# Main_Core.net
KiCad netlist of a schematic drawn in Altium Designer
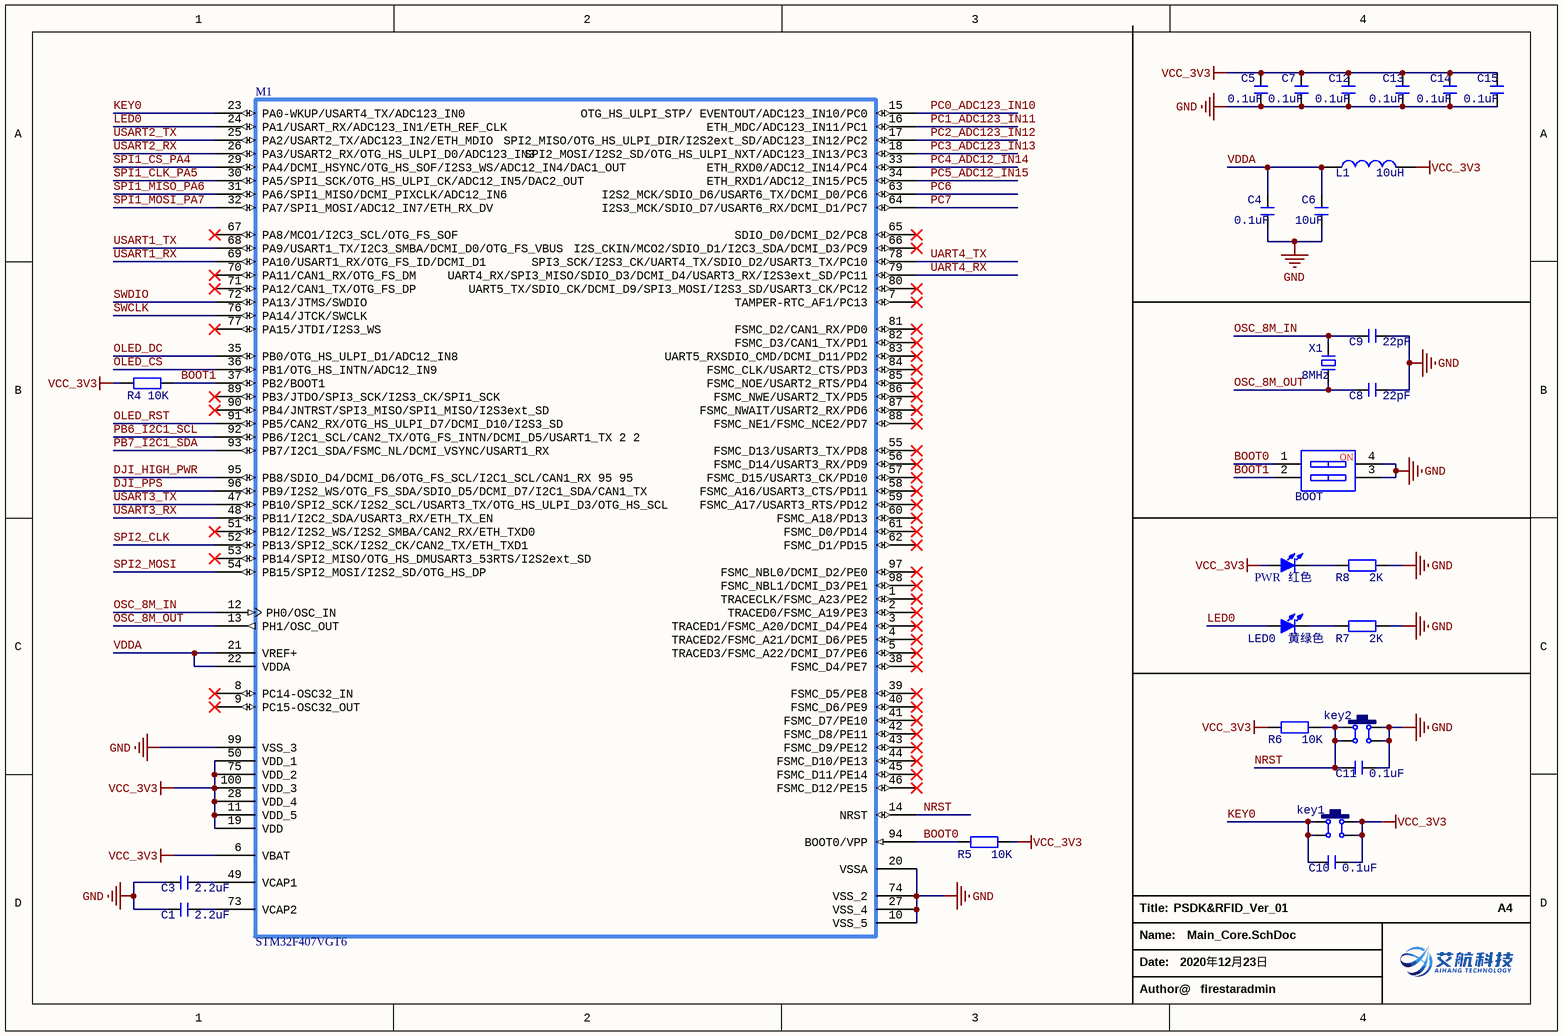
[diagram p0: Main_Core.SchDoc]

(export (version "E")
  (design (tool "Eeschema 10.0.6"))
  (components
    (comp (ref "BOOT")
      (value "CSW-2P")
      (footprint "CSW1.27 SMD-2P")
      (description "2路编码开关")
      (fields (field (name "版权归属") "源创客"))
      (libsource (lib "SCH-按键-开关") (part "CSW-2P"))
    )
    (comp (ref "C1")
      (value "2.2uF")
      (footprint "C 0603_L")
      (description "无极性贴片电容")
      (fields (field (name "版权归属") "源创客"))
      (libsource (lib "SCH-电阻-电容-电感") (part "C"))
    )
    (comp (ref "C3")
      (value "2.2uF")
      (footprint "C 0603_L")
      (description "无极性贴片电容")
      (fields (field (name "版权归属") "源创客"))
      (libsource (lib "SCH-电阻-电容-电感") (part "C"))
    )
    (comp (ref "C4")
      (value "0.1uF")
      (footprint "C 0603_L")
      (description "无极性贴片电容")
      (fields (field (name "版权归属") "源创客"))
      (libsource (lib "SCH-电阻-电容-电感") (part "C"))
    )
    (comp (ref "C5")
      (value "0.1uF")
      (footprint "C 0603_L")
      (description "无极性贴片电容")
      (fields (field (name "版权归属") "源创客"))
      (libsource (lib "SCH-电阻-电容-电感") (part "C"))
    )
    (comp (ref "C6")
      (value "10uF")
      (footprint "C 0603_L")
      (description "无极性贴片电容")
      (fields (field (name "版权归属") "源创客"))
      (libsource (lib "SCH-电阻-电容-电感") (part "C"))
    )
    (comp (ref "C7")
      (value "0.1uF")
      (footprint "C 0603_L")
      (description "无极性贴片电容")
      (fields (field (name "版权归属") "源创客"))
      (libsource (lib "SCH-电阻-电容-电感") (part "C"))
    )
    (comp (ref "C8")
      (value "22pF")
      (footprint "C 0603_L")
      (description "无极性贴片电容")
      (fields (field (name "版权归属") "源创客"))
      (libsource (lib "SCH-电阻-电容-电感") (part "C"))
    )
    (comp (ref "C9")
      (value "22pF")
      (footprint "C 0603_L")
      (description "无极性贴片电容")
      (fields (field (name "版权归属") "源创客"))
      (libsource (lib "SCH-电阻-电容-电感") (part "C"))
    )
    (comp (ref "C10")
      (value "0.1uF")
      (footprint "C 0603_L")
      (description "无极性贴片电容")
      (fields (field (name "版权归属") "源创客"))
      (libsource (lib "SCH-电阻-电容-电感") (part "C"))
    )
    (comp (ref "C11")
      (value "0.1uF")
      (footprint "C 0603_L")
      (description "无极性贴片电容")
      (fields (field (name "版权归属") "源创客"))
      (libsource (lib "SCH-电阻-电容-电感") (part "C"))
    )
    (comp (ref "C12")
      (value "0.1uF")
      (footprint "C 0603_L")
      (description "无极性贴片电容")
      (fields (field (name "版权归属") "源创客"))
      (libsource (lib "SCH-电阻-电容-电感") (part "C"))
    )
    (comp (ref "C13")
      (value "0.1uF")
      (footprint "C 0603_L")
      (description "无极性贴片电容")
      (fields (field (name "版权归属") "源创客"))
      (libsource (lib "SCH-电阻-电容-电感") (part "C"))
    )
    (comp (ref "C14")
      (value "0.1uF")
      (footprint "C 0603_L")
      (description "无极性贴片电容")
      (fields (field (name "版权归属") "源创客"))
      (libsource (lib "SCH-电阻-电容-电感") (part "C"))
    )
    (comp (ref "C15")
      (value "0.1uF")
      (footprint "C 0603_L")
      (description "无极性贴片电容")
      (fields (field (name "版权归属") "源创客"))
      (libsource (lib "SCH-电阻-电容-电感") (part "C"))
    )
    (comp (ref "key1")
      (value "key")
      (footprint "TSMD-3*4*2.5")
      (description "TS-3x4x2.5mm-4pin 轻触按键")
      (libsource (lib "SCH-按键-开关") (part "TS-3x4x2.5mm-4pin"))
    )
    (comp (ref "key2")
      (value "key")
      (footprint "TSMD-3*4*2.5")
      (description "TS-3x4x2.5mm-4pin 轻触按键")
      (libsource (lib "SCH-按键-开关") (part "TS-3x4x2.5mm-4pin"))
    )
    (comp (ref "L1")
      (value "10uH")
      (footprint "L 0603")
      (description "小功率贴片电感")
      (fields (field (name "版权归属") "源创客"))
      (libsource (lib "SCH-电阻-电容-电感") (part "L"))
    )
    (comp (ref "LED0")
      (value "黄绿色")
      (footprint "LED 0603G")
      (description "贴片LED")
      (fields (field (name "版权归属") "源创客"))
      (libsource (lib "SCH-LED") (part "LED-SMD"))
    )
    (comp (ref "M1")
      (value "STM32F407VGT6")
      (footprint "LQFP100 14x14_M")
      (description "LQFP100，ARM®-Cortex®-M4-series-微控制器-IC-32-位-168MHz-1MB Flash，192KB SRAM.  IO:82")
      (libsource (lib "SCH-STM32系列单片机") (part "STM32F407VGT6"))
    )
    (comp (ref "PWR")
      (value "红色")
      (footprint "LED 0603R")
      (description "贴片LED")
      (fields (field (name "版权归属") "源创客"))
      (libsource (lib "SCH-LED") (part "LED-SMD"))
    )
    (comp (ref "R4")
      (value "10K")
      (footprint "R 0603_L")
      (description "贴片电阻")
      (fields (field (name "版权归属") "源创客"))
      (libsource (lib "SCH-电阻-电容-电感") (part "R"))
    )
    (comp (ref "R5")
      (value "10K")
      (footprint "R 0603_L")
      (description "贴片电阻")
      (fields (field (name "版权归属") "源创客"))
      (libsource (lib "SCH-电阻-电容-电感") (part "R"))
    )
    (comp (ref "R6")
      (value "10K")
      (footprint "R 0603_L")
      (description "贴片电阻")
      (fields (field (name "版权归属") "源创客"))
      (libsource (lib "SCH-电阻-电容-电感") (part "R"))
    )
    (comp (ref "R7")
      (value "2K")
      (footprint "R 0603_L")
      (description "贴片电阻")
      (fields (field (name "版权归属") "源创客"))
      (libsource (lib "SCH-电阻-电容-电感") (part "R"))
    )
    (comp (ref "R8")
      (value "2K")
      (footprint "R 0603_L")
      (description "贴片电阻")
      (fields (field (name "版权归属") "源创客"))
      (libsource (lib "SCH-电阻-电容-电感") (part "R"))
    )
    (comp (ref "X1")
      (value "8MHz")
      (footprint "OSC 5032-2P")
      (description "2脚无源脚晶振")
      (fields (field (name "版权归属") "源创客"))
      (libsource (lib "SCH- 保险丝-晶振") (part "XTAL-2P"))
    )
  )
  (nets
    (net (code "1") (name "/BOOT0") (class "Default")
      (node (ref "BOOT") (pin "1") (pinfunction "1_1") (pintype "passive"))
      (node (ref "M1") (pin "94") (pinfunction "BOOT0/VPP_94") (pintype "input"))
      (node (ref "R5") (pin "1") (pinfunction "1_1") (pintype "passive"))
    )
    (net (code "2") (name "/BOOT1") (class "Default")
      (node (ref "BOOT") (pin "2") (pinfunction "2_2") (pintype "passive"))
      (node (ref "M1") (pin "37") (pinfunction "PB2/BOOT1_37") (pintype "bidirectional"))
      (node (ref "R4") (pin "1") (pinfunction "1_1") (pintype "passive"))
    )
    (net (code "3") (name "/DJI_HIGH_PWR") (class "Default")
      (node (ref "M1") (pin "95") (pinfunction "PB8/SDIO_D4/DCMI_D6/OTG_FS_SCL/I2C1_SCL/CAN1_RX_95_95_95") (pintype "bidirectional"))
    )
    (net (code "4") (name "/DJI_PPS") (class "Default")
      (node (ref "M1") (pin "96") (pinfunction "PB9/I2S2_WS/OTG_FS_SDA/SDIO_D5/DCMI_D7/I2C1_SDA/CAN1_TX_96") (pintype "bidirectional"))
    )
    (net (code "5") (name "/KEY0") (class "Default")
      (node (ref "C10") (pin "2") (pinfunction "2_2") (pintype "passive"))
      (node (ref "M1") (pin "23") (pinfunction "PA0-WKUP/USART4_TX/ADC123_IN0_23") (pintype "bidirectional"))
      (node (ref "key1") (pin "1") (pinfunction "1_1") (pintype "passive"))
      (node (ref "key1") (pin "2") (pinfunction "2_2") (pintype "passive"))
    )
    (net (code "6") (name "/LED0") (class "Default")
      (node (ref "LED0") (pin "1") (pinfunction "A_1") (pintype "passive"))
      (node (ref "M1") (pin "24") (pinfunction "PA1/USART_RX/ADC123_IN1/ETH_REF_CLK_24") (pintype "bidirectional"))
    )
    (net (code "7") (name "/NRST") (class "Default")
      (node (ref "C11") (pin "2") (pinfunction "2_2") (pintype "passive"))
      (node (ref "M1") (pin "14") (pinfunction "NRST_14") (pintype "bidirectional"))
      (node (ref "R6") (pin "2") (pinfunction "2_2") (pintype "passive"))
      (node (ref "key2") (pin "1") (pinfunction "1_1") (pintype "passive"))
      (node (ref "key2") (pin "2") (pinfunction "2_2") (pintype "passive"))
    )
    (net (code "8") (name "/OLED_CS") (class "Default")
      (node (ref "M1") (pin "36") (pinfunction "PB1/OTG_HS_INTN/ADC12_IN9_36") (pintype "bidirectional"))
    )
    (net (code "9") (name "/OLED_DC") (class "Default")
      (node (ref "M1") (pin "35") (pinfunction "PB0/OTG_HS_ULPI_D1/ADC12_IN8_35") (pintype "bidirectional"))
    )
    (net (code "10") (name "/OLED_RST") (class "Default")
      (node (ref "M1") (pin "91") (pinfunction "PB5/CAN2_RX/OTG_HS_ULPI_D7/DCMI_D10/I2S3_SD_91") (pintype "bidirectional"))
    )
    (net (code "11") (name "/OSC_8M_IN") (class "Default")
      (node (ref "C9") (pin "2") (pinfunction "2_2") (pintype "passive"))
      (node (ref "M1") (pin "12") (pinfunction "PH0/OSC_IN_12") (pintype "input"))
      (node (ref "X1") (pin "2") (pinfunction "2_2") (pintype "passive"))
    )
    (net (code "12") (name "/OSC_8M_OUT") (class "Default")
      (node (ref "C8") (pin "2") (pinfunction "2_2") (pintype "passive"))
      (node (ref "M1") (pin "13") (pinfunction "PH1/OSC_OUT_13") (pintype "output"))
      (node (ref "X1") (pin "1") (pinfunction "1_1") (pintype "passive"))
    )
    (net (code "13") (name "/PB6_I2C1_SCL") (class "Default")
      (node (ref "M1") (pin "92") (pinfunction "PB6/I2C1_SCL/CAN2_TX/OTG_FS_INTN/DCMI_D5/USART1_TX_2_2_92") (pintype "bidirectional"))
    )
    (net (code "14") (name "/PB7_I2C1_SDA") (class "Default")
      (node (ref "M1") (pin "93") (pinfunction "PB7/I2C1_SDA/FSMC_NL/DCMI_VSYNC/USART1_RX_93") (pintype "bidirectional"))
    )
    (net (code "15") (name "/PC0_ADC123_IN10") (class "Default")
      (node (ref "M1") (pin "15") (pinfunction "OTG_HS_ULPI_STP/_EVENTOUT/ADC123_IN10/PC0_15") (pintype "bidirectional"))
    )
    (net (code "16") (name "/PC1_ADC123_IN11") (class "Default")
      (node (ref "M1") (pin "16") (pinfunction "ETH_MDC/ADC123_IN11/PC1_16") (pintype "bidirectional"))
    )
    (net (code "17") (name "/PC2_ADC123_IN12") (class "Default")
      (node (ref "M1") (pin "17") (pinfunction "SPI2_MISO/OTG_HS_ULPI_DIR/I2S2ext_SD/ADC123_IN12/PC2_17") (pintype "bidirectional"))
    )
    (net (code "18") (name "/PC3_ADC123_IN13") (class "Default")
      (node (ref "M1") (pin "18") (pinfunction "SPI2_MOSI/I2S2_SD/OTG_HS_ULPI_NXT/ADC123_IN13/PC3_18") (pintype "bidirectional"))
    )
    (net (code "19") (name "/PC4_ADC12_IN14") (class "Default")
      (node (ref "M1") (pin "33") (pinfunction "ETH_RXD0/ADC12_IN14/PC4_33") (pintype "bidirectional"))
    )
    (net (code "20") (name "/PC5_ADC12_IN15") (class "Default")
      (node (ref "M1") (pin "34") (pinfunction "ETH_RXD1/ADC12_IN15/PC5_34") (pintype "bidirectional"))
    )
    (net (code "21") (name "/PC6") (class "Default")
      (node (ref "M1") (pin "63") (pinfunction "I2S2_MCK/SDIO_D6/USART6_TX/DCMI_D0/PC6_63") (pintype "bidirectional"))
    )
    (net (code "22") (name "/PC7") (class "Default")
      (node (ref "M1") (pin "64") (pinfunction "I2S3_MCK/SDIO_D7/USART6_RX/DCMI_D1/PC7_64") (pintype "bidirectional"))
    )
    (net (code "23") (name "/SPI1_CLK_PA5") (class "Default")
      (node (ref "M1") (pin "30") (pinfunction "PA5/SPI1_SCK/OTG_HS_ULPI_CK/ADC12_IN5/DAC2_OUT_30") (pintype "bidirectional"))
    )
    (net (code "24") (name "/SPI1_CS_PA4") (class "Default")
      (node (ref "M1") (pin "29") (pinfunction "PA4/DCMI_HSYNC/OTG_HS_SOF/I2S3_WS/ADC12_IN4/DAC1_OUT_29") (pintype "bidirectional"))
    )
    (net (code "25") (name "/SPI1_MISO_PA6") (class "Default")
      (node (ref "M1") (pin "31") (pinfunction "PA6/SPI1_MISO/DCMI_PIXCLK/ADC12_IN6_31") (pintype "bidirectional"))
    )
    (net (code "26") (name "/SPI1_MOSI_PA7") (class "Default")
      (node (ref "M1") (pin "32") (pinfunction "PA7/SPI1_MOSI/ADC12_IN7/ETH_RX_DV_32") (pintype "bidirectional"))
    )
    (net (code "27") (name "/SPI2_CLK") (class "Default")
      (node (ref "M1") (pin "52") (pinfunction "PB13/SPI2_SCK/I2S2_CK/CAN2_TX/ETH_TXD1_52") (pintype "bidirectional"))
    )
    (net (code "28") (name "/SPI2_MOSI") (class "Default")
      (node (ref "M1") (pin "54") (pinfunction "PB15/SPI2_MOSI/I2S2_SD/OTG_HS_DP_54") (pintype "bidirectional"))
    )
    (net (code "29") (name "/SWCLK") (class "Default")
      (node (ref "M1") (pin "76") (pinfunction "PA14/JTCK/SWCLK_76") (pintype "bidirectional"))
    )
    (net (code "30") (name "/SWDIO") (class "Default")
      (node (ref "M1") (pin "72") (pinfunction "PA13/JTMS/SWDIO_72") (pintype "bidirectional"))
    )
    (net (code "31") (name "/UART4_RX") (class "Default")
      (node (ref "M1") (pin "79") (pinfunction "UART4_RX/SPI3_MISO/SDIO_D3/DCMI_D4/USART3_RX/I2S3ext_SD/PC11_79") (pintype "bidirectional"))
    )
    (net (code "32") (name "/UART4_TX") (class "Default")
      (node (ref "M1") (pin "78") (pinfunction "SPI3_SCK/I2S3_CK/UART4_TX/SDIO_D2/USART3_TX/PC10_78") (pintype "bidirectional"))
    )
    (net (code "33") (name "/USART1_RX") (class "Default")
      (node (ref "M1") (pin "69") (pinfunction "PA10/USART1_RX/OTG_FS_ID/DCMI_D1_69") (pintype "bidirectional"))
    )
    (net (code "34") (name "/USART1_TX") (class "Default")
      (node (ref "M1") (pin "68") (pinfunction "PA9/USART1_TX/I2C3_SMBA/DCMI_D0/OTG_FS_VBUS_68") (pintype "bidirectional"))
    )
    (net (code "35") (name "/USART2_RX") (class "Default")
      (node (ref "M1") (pin "26") (pinfunction "PA3/USART2_RX/OTG_HS_ULPI_D0/ADC123_IN3_26") (pintype "bidirectional"))
    )
    (net (code "36") (name "/USART2_TX") (class "Default")
      (node (ref "M1") (pin "25") (pinfunction "PA2/USART2_TX/ADC123_IN2/ETH_MDIO_25") (pintype "bidirectional"))
    )
    (net (code "37") (name "/USART3_RX") (class "Default")
      (node (ref "M1") (pin "48") (pinfunction "PB11/I2C2_SDA/USART3_RX/ETH_TX_EN_48") (pintype "bidirectional"))
    )
    (net (code "38") (name "/USART3_TX") (class "Default")
      (node (ref "M1") (pin "47") (pinfunction "PB10/SPI2_SCK/I2S2_SCL/USART3_TX/OTG_HS_ULPI_D3/OTG_HS_SCL_47") (pintype "bidirectional"))
    )
    (net (code "39") (name "/VDDA") (class "Default")
      (node (ref "C4") (pin "2") (pinfunction "2_2") (pintype "passive"))
      (node (ref "C6") (pin "2") (pinfunction "2_2") (pintype "passive"))
      (node (ref "L1") (pin "1") (pinfunction "1_1") (pintype "passive"))
      (node (ref "M1") (pin "21") (pinfunction "VREF+_21") (pintype "power_in"))
      (node (ref "M1") (pin "22") (pinfunction "VDDA_22") (pintype "power_in"))
    )
    (net (code "40") (name "GND") (class "Default")
      (node (ref "BOOT") (pin "3") (pinfunction "3_3") (pintype "passive"))
      (node (ref "BOOT") (pin "4") (pinfunction "4_4") (pintype "passive"))
      (node (ref "C1") (pin "2") (pinfunction "2_2") (pintype "passive"))
      (node (ref "C11") (pin "1") (pinfunction "1_1") (pintype "passive"))
      (node (ref "C12") (pin "1") (pinfunction "1_1") (pintype "passive"))
      (node (ref "C13") (pin "1") (pinfunction "1_1") (pintype "passive"))
      (node (ref "C14") (pin "1") (pinfunction "1_1") (pintype "passive"))
      (node (ref "C15") (pin "1") (pinfunction "1_1") (pintype "passive"))
      (node (ref "C3") (pin "2") (pinfunction "2_2") (pintype "passive"))
      (node (ref "C4") (pin "1") (pinfunction "1_1") (pintype "passive"))
      (node (ref "C5") (pin "1") (pinfunction "1_1") (pintype "passive"))
      (node (ref "C6") (pin "1") (pinfunction "1_1") (pintype "passive"))
      (node (ref "C7") (pin "1") (pinfunction "1_1") (pintype "passive"))
      (node (ref "C8") (pin "1") (pinfunction "1_1") (pintype "passive"))
      (node (ref "C9") (pin "1") (pinfunction "1_1") (pintype "passive"))
      (node (ref "M1") (pin "10") (pinfunction "VSS_5_10") (pintype "power_in"))
      (node (ref "M1") (pin "20") (pinfunction "VSSA_20") (pintype "power_in"))
      (node (ref "M1") (pin "27") (pinfunction "VSS_4_27") (pintype "power_in"))
      (node (ref "M1") (pin "74") (pinfunction "VSS_2_74") (pintype "power_in"))
      (node (ref "M1") (pin "99") (pinfunction "VSS_3_99") (pintype "power_in"))
      (node (ref "R7") (pin "2") (pinfunction "2_2") (pintype "passive"))
      (node (ref "R8") (pin "2") (pinfunction "2_2") (pintype "passive"))
      (node (ref "key2") (pin "3") (pinfunction "3_3") (pintype "passive"))
      (node (ref "key2") (pin "4") (pinfunction "4_4") (pintype "passive"))
    )
    (net (code "41") (name "Net-(LED0-K)") (class "Default")
      (node (ref "LED0") (pin "2") (pinfunction "K_2") (pintype "passive"))
      (node (ref "R7") (pin "1") (pinfunction "1_1") (pintype "passive"))
    )
    (net (code "42") (name "Net-(M1-VCAP1)") (class "Default")
      (node (ref "C3") (pin "1") (pinfunction "1_1") (pintype "passive"))
      (node (ref "M1") (pin "49") (pinfunction "VCAP1_49") (pintype "power_in"))
    )
    (net (code "43") (name "Net-(M1-VCAP2)") (class "Default")
      (node (ref "C1") (pin "1") (pinfunction "1_1") (pintype "passive"))
      (node (ref "M1") (pin "73") (pinfunction "VCAP2_73") (pintype "passive"))
    )
    (net (code "44") (name "Net-(PWR-K)") (class "Default")
      (node (ref "PWR") (pin "2") (pinfunction "K_2") (pintype "passive"))
      (node (ref "R8") (pin "1") (pinfunction "1_1") (pintype "passive"))
    )
    (net (code "45") (name "VCC_3V3") (class "Default")
      (node (ref "C10") (pin "1") (pinfunction "1_1") (pintype "passive"))
      (node (ref "C12") (pin "2") (pinfunction "2_2") (pintype "passive"))
      (node (ref "C13") (pin "2") (pinfunction "2_2") (pintype "passive"))
      (node (ref "C14") (pin "2") (pinfunction "2_2") (pintype "passive"))
      (node (ref "C15") (pin "2") (pinfunction "2_2") (pintype "passive"))
      (node (ref "C5") (pin "2") (pinfunction "2_2") (pintype "passive"))
      (node (ref "C7") (pin "2") (pinfunction "2_2") (pintype "passive"))
      (node (ref "L1") (pin "2") (pinfunction "2_2") (pintype "passive"))
      (node (ref "M1") (pin "100") (pinfunction "VDD_3_100") (pintype "power_in"))
      (node (ref "M1") (pin "11") (pinfunction "VDD_5_11") (pintype "power_in"))
      (node (ref "M1") (pin "19") (pinfunction "VDD_19") (pintype "power_in"))
      (node (ref "M1") (pin "28") (pinfunction "VDD_4_28") (pintype "power_in"))
      (node (ref "M1") (pin "50") (pinfunction "VDD_1_50") (pintype "power_in"))
      (node (ref "M1") (pin "6") (pinfunction "VBAT_6") (pintype "power_in"))
      (node (ref "M1") (pin "75") (pinfunction "VDD_2_75") (pintype "power_in"))
      (node (ref "PWR") (pin "1") (pinfunction "A_1") (pintype "passive"))
      (node (ref "R4") (pin "2") (pinfunction "2_2") (pintype "passive"))
      (node (ref "R5") (pin "2") (pinfunction "2_2") (pintype "passive"))
      (node (ref "R6") (pin "1") (pinfunction "1_1") (pintype "passive"))
      (node (ref "key1") (pin "3") (pinfunction "3_3") (pintype "passive"))
      (node (ref "key1") (pin "4") (pinfunction "4_4") (pintype "passive"))
    )
    (net (code "46") (name "unconnected-(M1-FSMC_A16{slash}USART3_CTS{slash}PD11-Pad58)") (class "Default")
      (node (ref "M1") (pin "58") (pinfunction "FSMC_A16/USART3_CTS/PD11_58") (pintype "bidirectional+no_connect"))
    )
    (net (code "47") (name "unconnected-(M1-FSMC_A17{slash}USART3_RTS{slash}PD12-Pad59)") (class "Default")
      (node (ref "M1") (pin "59") (pinfunction "FSMC_A17/USART3_RTS/PD12_59") (pintype "bidirectional+no_connect"))
    )
    (net (code "48") (name "unconnected-(M1-FSMC_A18{slash}PD13-Pad60)") (class "Default")
      (node (ref "M1") (pin "60") (pinfunction "FSMC_A18/PD13_60") (pintype "bidirectional+no_connect"))
    )
    (net (code "49") (name "unconnected-(M1-FSMC_CLK{slash}USART2_CTS{slash}PD3-Pad84)") (class "Default")
      (node (ref "M1") (pin "84") (pinfunction "FSMC_CLK/USART2_CTS/PD3_84") (pintype "bidirectional+no_connect"))
    )
    (net (code "50") (name "unconnected-(M1-FSMC_D0{slash}PD14-Pad61)") (class "Default")
      (node (ref "M1") (pin "61") (pinfunction "FSMC_D0/PD14_61") (pintype "bidirectional+no_connect"))
    )
    (net (code "51") (name "unconnected-(M1-FSMC_D1{slash}PD15-Pad62)") (class "Default")
      (node (ref "M1") (pin "62") (pinfunction "FSMC_D1/PD15_62") (pintype "bidirectional+no_connect"))
    )
    (net (code "52") (name "unconnected-(M1-FSMC_D2{slash}CAN1_RX{slash}PD0-Pad81)") (class "Default")
      (node (ref "M1") (pin "81") (pinfunction "FSMC_D2/CAN1_RX/PD0_81") (pintype "bidirectional+no_connect"))
    )
    (net (code "53") (name "unconnected-(M1-FSMC_D3{slash}CAN1_TX{slash}PD1-Pad82)") (class "Default")
      (node (ref "M1") (pin "82") (pinfunction "FSMC_D3/CAN1_TX/PD1_82") (pintype "bidirectional+no_connect"))
    )
    (net (code "54") (name "unconnected-(M1-FSMC_D4{slash}PE7-Pad38)") (class "Default")
      (node (ref "M1") (pin "38") (pinfunction "FSMC_D4/PE7_38") (pintype "bidirectional+no_connect"))
    )
    (net (code "55") (name "unconnected-(M1-FSMC_D5{slash}PE8-Pad39)") (class "Default")
      (node (ref "M1") (pin "39") (pinfunction "FSMC_D5/PE8_39") (pintype "bidirectional+no_connect"))
    )
    (net (code "56") (name "unconnected-(M1-FSMC_D6{slash}PE9-Pad40)") (class "Default")
      (node (ref "M1") (pin "40") (pinfunction "FSMC_D6/PE9_40") (pintype "bidirectional+no_connect"))
    )
    (net (code "57") (name "unconnected-(M1-FSMC_D7{slash}PE10-Pad41)") (class "Default")
      (node (ref "M1") (pin "41") (pinfunction "FSMC_D7/PE10_41") (pintype "bidirectional+no_connect"))
    )
    (net (code "58") (name "unconnected-(M1-FSMC_D8{slash}PE11-Pad42)") (class "Default")
      (node (ref "M1") (pin "42") (pinfunction "FSMC_D8/PE11_42") (pintype "bidirectional+no_connect"))
    )
    (net (code "59") (name "unconnected-(M1-FSMC_D9{slash}PE12-Pad43)") (class "Default")
      (node (ref "M1") (pin "43") (pinfunction "FSMC_D9/PE12_43") (pintype "bidirectional+no_connect"))
    )
    (net (code "60") (name "unconnected-(M1-FSMC_D10{slash}PE13-Pad44)") (class "Default")
      (node (ref "M1") (pin "44") (pinfunction "FSMC_D10/PE13_44") (pintype "bidirectional+no_connect"))
    )
    (net (code "61") (name "unconnected-(M1-FSMC_D11{slash}PE14-Pad45)") (class "Default")
      (node (ref "M1") (pin "45") (pinfunction "FSMC_D11/PE14_45") (pintype "bidirectional+no_connect"))
    )
    (net (code "62") (name "unconnected-(M1-FSMC_D12{slash}PE15-Pad46)") (class "Default")
      (node (ref "M1") (pin "46") (pinfunction "FSMC_D12/PE15_46") (pintype "bidirectional+no_connect"))
    )
    (net (code "63") (name "unconnected-(M1-FSMC_D13{slash}USART3_TX{slash}PD8-Pad55)") (class "Default")
      (node (ref "M1") (pin "55") (pinfunction "FSMC_D13/USART3_TX/PD8_55") (pintype "bidirectional+no_connect"))
    )
    (net (code "64") (name "unconnected-(M1-FSMC_D14{slash}USART3_RX{slash}PD9-Pad56)") (class "Default")
      (node (ref "M1") (pin "56") (pinfunction "FSMC_D14/USART3_RX/PD9_56") (pintype "bidirectional+no_connect"))
    )
    (net (code "65") (name "unconnected-(M1-FSMC_D15{slash}USART3_CK{slash}PD10-Pad57)") (class "Default")
      (node (ref "M1") (pin "57") (pinfunction "FSMC_D15/USART3_CK/PD10_57") (pintype "bidirectional+no_connect"))
    )
    (net (code "66") (name "unconnected-(M1-FSMC_NBL0{slash}DCMI_D2{slash}PE0-Pad97)") (class "Default")
      (node (ref "M1") (pin "97") (pinfunction "FSMC_NBL0/DCMI_D2/PE0_97") (pintype "bidirectional+no_connect"))
    )
    (net (code "67") (name "unconnected-(M1-FSMC_NBL1{slash}DCMI_D3{slash}PE1-Pad98)") (class "Default")
      (node (ref "M1") (pin "98") (pinfunction "FSMC_NBL1/DCMI_D3/PE1_98") (pintype "bidirectional+no_connect"))
    )
    (net (code "68") (name "unconnected-(M1-FSMC_NE1{slash}FSMC_NCE2{slash}PD7-Pad88)") (class "Default")
      (node (ref "M1") (pin "88") (pinfunction "FSMC_NE1/FSMC_NCE2/PD7_88") (pintype "bidirectional+no_connect"))
    )
    (net (code "69") (name "unconnected-(M1-FSMC_NOE{slash}USART2_RTS{slash}PD4-Pad85)") (class "Default")
      (node (ref "M1") (pin "85") (pinfunction "FSMC_NOE/USART2_RTS/PD4_85") (pintype "bidirectional+no_connect"))
    )
    (net (code "70") (name "unconnected-(M1-FSMC_NWAIT{slash}USART2_RX{slash}PD6-Pad87)") (class "Default")
      (node (ref "M1") (pin "87") (pinfunction "FSMC_NWAIT/USART2_RX/PD6_87") (pintype "bidirectional+no_connect"))
    )
    (net (code "71") (name "unconnected-(M1-FSMC_NWE{slash}USART2_TX{slash}PD5-Pad86)") (class "Default")
      (node (ref "M1") (pin "86") (pinfunction "FSMC_NWE/USART2_TX/PD5_86") (pintype "bidirectional+no_connect"))
    )
    (net (code "72") (name "unconnected-(M1-I2S_CKIN{slash}MCO2{slash}SDIO_D1{slash}I2C3_SDA{slash}DCMI_D3{slash}PC9-Pad66)") (class "Default")
      (node (ref "M1") (pin "66") (pinfunction "I2S_CKIN/MCO2/SDIO_D1/I2C3_SDA/DCMI_D3/PC9_66") (pintype "bidirectional+no_connect"))
    )
    (net (code "73") (name "unconnected-(M1-PA8{slash}MCO1{slash}I2C3_SCL{slash}OTG_FS_SOF-Pad67)") (class "Default")
      (node (ref "M1") (pin "67") (pinfunction "PA8/MCO1/I2C3_SCL/OTG_FS_SOF_67") (pintype "bidirectional+no_connect"))
    )
    (net (code "74") (name "unconnected-(M1-PA11{slash}CAN1_RX{slash}OTG_FS_DM-Pad70)") (class "Default")
      (node (ref "M1") (pin "70") (pinfunction "PA11/CAN1_RX/OTG_FS_DM_70") (pintype "bidirectional+no_connect"))
    )
    (net (code "75") (name "unconnected-(M1-PA12{slash}CAN1_TX{slash}OTG_FS_DP-Pad71)") (class "Default")
      (node (ref "M1") (pin "71") (pinfunction "PA12/CAN1_TX/OTG_FS_DP_71") (pintype "bidirectional+no_connect"))
    )
    (net (code "76") (name "unconnected-(M1-PA15{slash}JTDI{slash}I2S3_WS-Pad77)") (class "Default")
      (node (ref "M1") (pin "77") (pinfunction "PA15/JTDI/I2S3_WS_77") (pintype "bidirectional+no_connect"))
    )
    (net (code "77") (name "unconnected-(M1-PB3{slash}JTDO{slash}SPI3_SCK{slash}I2S3_CK{slash}SPI1_SCK-Pad89)") (class "Default")
      (node (ref "M1") (pin "89") (pinfunction "PB3/JTDO/SPI3_SCK/I2S3_CK/SPI1_SCK_89") (pintype "bidirectional+no_connect"))
    )
    (net (code "78") (name "unconnected-(M1-PB4{slash}JNTRST{slash}SPI3_MISO{slash}SPI1_MISO{slash}I2S3ext_SD-Pad90)") (class "Default")
      (node (ref "M1") (pin "90") (pinfunction "PB4/JNTRST/SPI3_MISO/SPI1_MISO/I2S3ext_SD_90") (pintype "bidirectional+no_connect"))
    )
    (net (code "79") (name "unconnected-(M1-PB12{slash}I2S2_WS{slash}I2S2_SMBA{slash}CAN2_RX{slash}ETH_TXD0-Pad51)") (class "Default")
      (node (ref "M1") (pin "51") (pinfunction "PB12/I2S2_WS/I2S2_SMBA/CAN2_RX/ETH_TXD0_51") (pintype "bidirectional+no_connect"))
    )
    (net (code "80") (name "unconnected-(M1-PB14{slash}SPI2_MISO{slash}OTG_HS_DMUSART3_53RTS{slash}I2S2ext_SD-Pad53)") (class "Default")
      (node (ref "M1") (pin "53") (pinfunction "PB14/SPI2_MISO/OTG_HS_DMUSART3_53RTS/I2S2ext_SD_53") (pintype "bidirectional+no_connect"))
    )
    (net (code "81") (name "unconnected-(M1-PC14-OSC32_IN-Pad8)") (class "Default")
      (node (ref "M1") (pin "8") (pinfunction "PC14-OSC32_IN_8") (pintype "bidirectional+no_connect"))
    )
    (net (code "82") (name "unconnected-(M1-PC15-OSC32_OUT-Pad9)") (class "Default")
      (node (ref "M1") (pin "9") (pinfunction "PC15-OSC32_OUT_9") (pintype "bidirectional+no_connect"))
    )
    (net (code "83") (name "unconnected-(M1-SDIO_D0{slash}DCMI_D2{slash}PC8-Pad65)") (class "Default")
      (node (ref "M1") (pin "65") (pinfunction "SDIO_D0/DCMI_D2/PC8_65") (pintype "bidirectional+no_connect"))
    )
    (net (code "84") (name "unconnected-(M1-TAMPER-RTC_AF1{slash}PC13-Pad7)") (class "Default")
      (node (ref "M1") (pin "7") (pinfunction "TAMPER-RTC_AF1/PC13_7") (pintype "bidirectional+no_connect"))
    )
    (net (code "85") (name "unconnected-(M1-TRACECLK{slash}FSMC_A23{slash}PE2-Pad1)") (class "Default")
      (node (ref "M1") (pin "1") (pinfunction "TRACECLK/FSMC_A23/PE2_1") (pintype "bidirectional+no_connect"))
    )
    (net (code "86") (name "unconnected-(M1-TRACED0{slash}FSMC_A19{slash}PE3-Pad2)") (class "Default")
      (node (ref "M1") (pin "2") (pinfunction "TRACED0/FSMC_A19/PE3_2") (pintype "bidirectional+no_connect"))
    )
    (net (code "87") (name "unconnected-(M1-TRACED1{slash}FSMC_A20{slash}DCMI_D4{slash}PE4-Pad3)") (class "Default")
      (node (ref "M1") (pin "3") (pinfunction "TRACED1/FSMC_A20/DCMI_D4/PE4_3") (pintype "bidirectional+no_connect"))
    )
    (net (code "88") (name "unconnected-(M1-TRACED2{slash}FSMC_A21{slash}DCMI_D6{slash}PE5-Pad4)") (class "Default")
      (node (ref "M1") (pin "4") (pinfunction "TRACED2/FSMC_A21/DCMI_D6/PE5_4") (pintype "bidirectional+no_connect"))
    )
    (net (code "89") (name "unconnected-(M1-TRACED3{slash}FSMC_A22{slash}DCMI_D7{slash}PE6-Pad5)") (class "Default")
      (node (ref "M1") (pin "5") (pinfunction "TRACED3/FSMC_A22/DCMI_D7/PE6_5") (pintype "bidirectional+no_connect"))
    )
    (net (code "90") (name "unconnected-(M1-UART5_RXSDIO_CMD{slash}DCMI_D11{slash}PD2-Pad83)") (class "Default")
      (node (ref "M1") (pin "83") (pinfunction "UART5_RXSDIO_CMD/DCMI_D11/PD2_83") (pintype "bidirectional+no_connect"))
    )
    (net (code "91") (name "unconnected-(M1-UART5_TX{slash}SDIO_CK{slash}DCMI_D9{slash}SPI3_MOSI{slash}I2S3_SD{slash}USART3_CK{slash}PC12-Pad80)") (class "Default")
      (node (ref "M1") (pin "80") (pinfunction "UART5_TX/SDIO_CK/DCMI_D9/SPI3_MOSI/I2S3_SD/USART3_CK/PC12_80") (pintype "bidirectional+no_connect"))
    )
  )
)
